# Main.net
KiCad netlist of a schematic drawn in Altium Designer
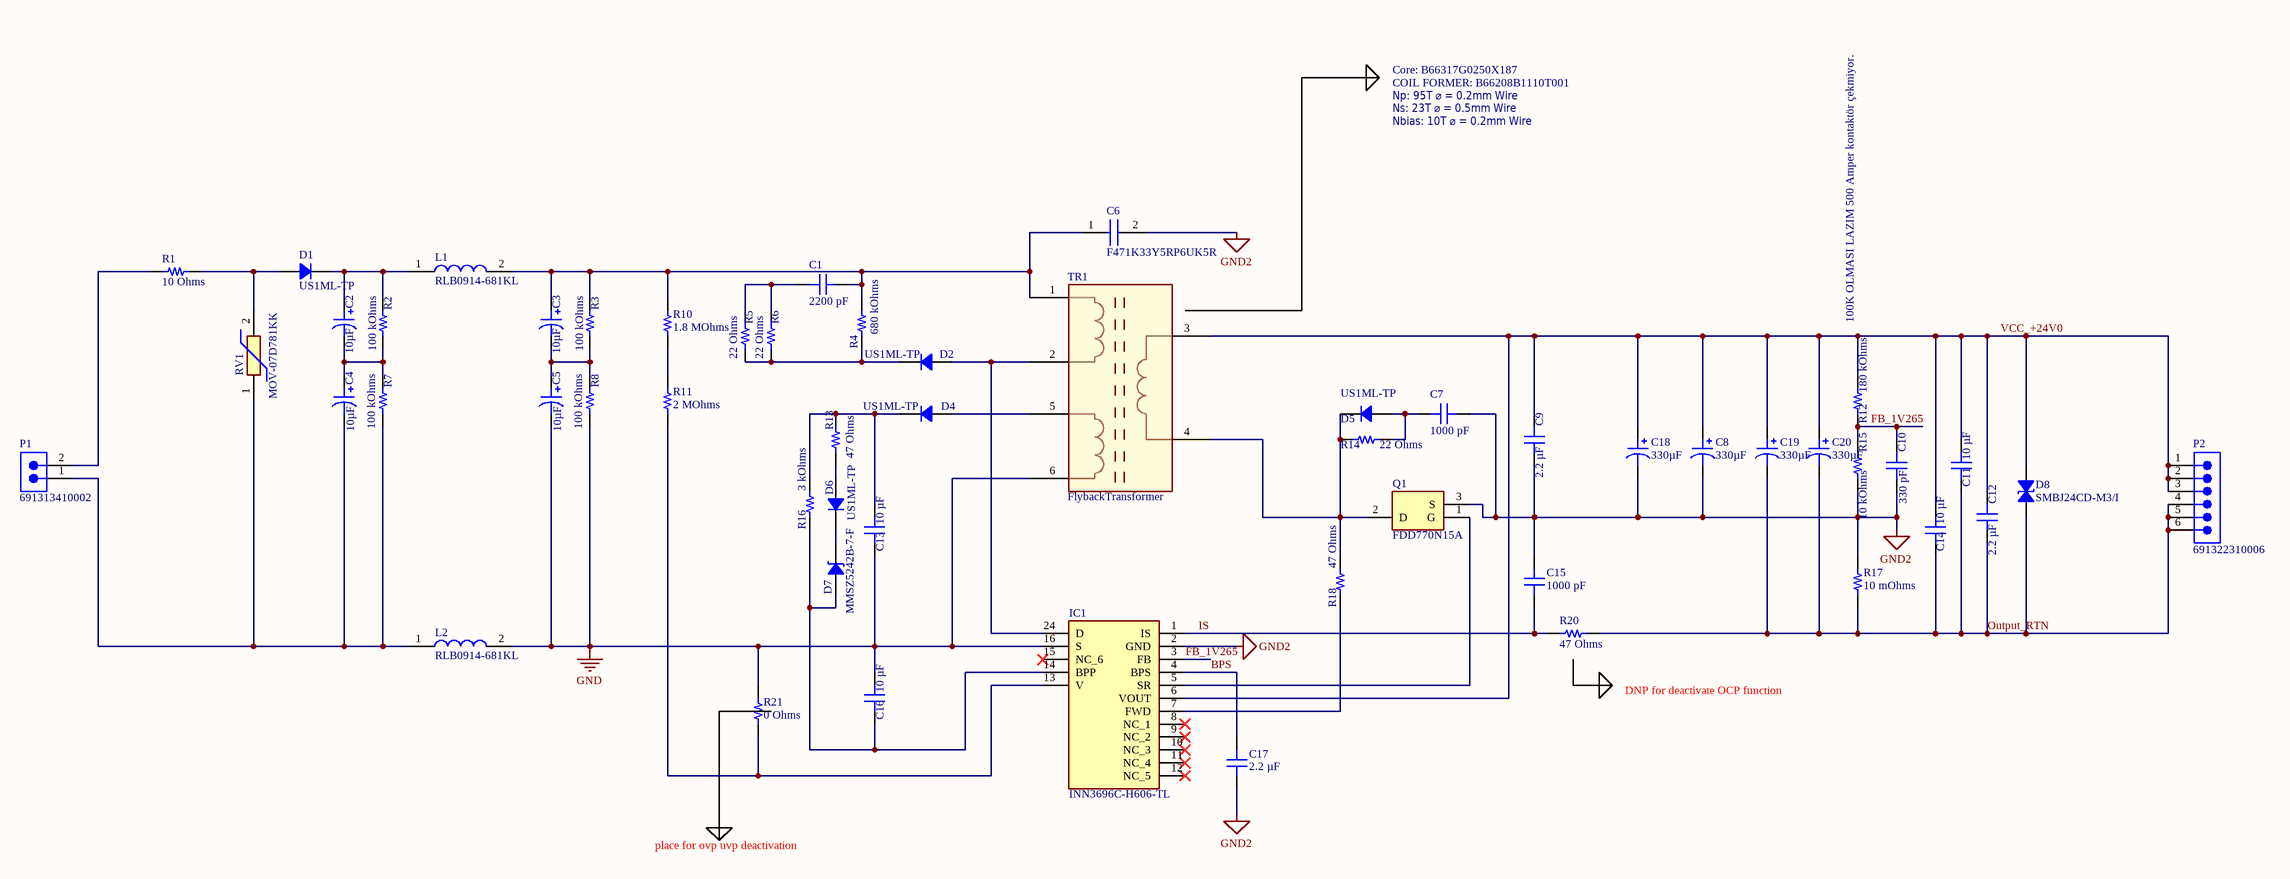
[diagram p0: Main.SchDoc]

(export (version "E")
  (design (tool "Eeschema 10.0.6"))
  (components
    (comp (ref "C1")
      (value "2200 pF")
      (footprint "CAP 1206_3216 - 0.8MM")
      (description "CAP CER 2200PF 2KV X7R 1206")
      (fields (field (name "MANUFACTURER") "KEMET") (field (name "TOLERANCE") "±10%"))
      (libsource (lib "Dannie Main") (part "CAPACITOR"))
    )
    (comp (ref "C2")
      (value "10µF")
      (footprint "CAP TH ALUM ELEC D10.00mm S5.00mm H17.00mm")
      (description "CAP ALUM 10UF 20% 400V THRUHOLE")
      (fields (field (name "PART NUMBER") "ESK106M400AH2EA") (field (name "TOLERANCE") "±20%"))
      (libsource (lib "Dannie Main") (part "POLARISED CAPACITOR"))
    )
    (comp (ref "C3")
      (value "10µF")
      (footprint "CAP TH ALUM ELEC D10.00mm S5.00mm H17.00mm")
      (description "CAP ALUM 10UF 20% 400V THRUHOLE")
      (fields (field (name "PART NUMBER") "ESK106M400AH2EA") (field (name "TOLERANCE") "±20%"))
      (libsource (lib "Dannie Main") (part "POLARISED CAPACITOR"))
    )
    (comp (ref "C4")
      (value "10µF")
      (footprint "CAP TH ALUM ELEC D10.00mm S5.00mm H17.00mm")
      (description "CAP ALUM 10UF 20% 400V THRUHOLE")
      (fields (field (name "PART NUMBER") "ESK106M400AH2EA") (field (name "TOLERANCE") "±20%"))
      (libsource (lib "Dannie Main") (part "POLARISED CAPACITOR"))
    )
    (comp (ref "C5")
      (value "10µF")
      (footprint "CAP TH ALUM ELEC D10.00mm S5.00mm H17.00mm")
      (description "CAP ALUM 10UF 20% 400V THRUHOLE")
      (fields (field (name "PART NUMBER") "ESK106M400AH2EA") (field (name "TOLERANCE") "±20%"))
      (libsource (lib "Dannie Main") (part "POLARISED CAPACITOR"))
    )
    (comp (ref "C6")
      (value "F471K33Y5RP6UK5R")
      (footprint "SamacSys:F471K33Y5RP6UK5R")
      (description "Capacitor")
      (fields (field (name "MOUSER PART NUMBER") "594-F471K33Y5RP6UK5R"))
      (libsource (lib "*") (part "F471K33Y5RP6UK5R"))
    )
    (comp (ref "C7")
      (value "1000 pF")
      (footprint "CAP 0603_1608")
      (description "CAP CER 1000PF 50V X7R 0603")
      (fields (field (name "MANUFACTURER") "Samsung Electro-Mechanics") (field (name "TOLERANCE") "±10%"))
      (libsource (lib "Dannie Main") (part "CAPACITOR"))
    )
    (comp (ref "C8")
      (value "330µF")
      (footprint "CAP TH ALUM ELEC D10.00mm S5.00mm H14.00mm")
      (description "CAP ALUM 330UF 20% 35V RADIAL")
      (fields (field (name "PART NUMBER") "UVY1V331MPD1TD") (field (name "MANUFACTURER") "Nichicon"))
      (libsource (lib "Dannie Main") (part "POLARISED CAPACITOR"))
    )
    (comp (ref "C9")
      (value "2.2 µF")
      (footprint "CAP 1206_3216 - 0.8MM")
      (description "CAP CER 2.2UF 50V X7R 1206")
      (fields (field (name "MANUFACTURER") "Samsung Electro-Mechanics") (field (name "TOLERANCE") "±10%"))
      (libsource (lib "Dannie Main") (part "CAPACITOR"))
    )
    (comp (ref "C10")
      (value "330 pF")
      (footprint "CAP 1206_3216 - 0.8MM")
      (description "CAP CER 330PF 50V X7R 1206")
      (fields (field (name "TOLERANCE") "±10%") (field (name "PART NUMBER") "885012208072"))
      (libsource (lib "Dannie Main") (part "CAPACITOR"))
    )
    (comp (ref "C11")
      (value "10 µF")
      (footprint "CAP 1206_3216 - 0.8MM")
      (description "CAP CER 10UF 50V X5R 1206")
      (fields (field (name "TOLERANCE") "±20%") (field (name "MANUFACTURER") "Samsung Electro-Mechanics"))
      (libsource (lib "Dannie Main") (part "CAPACITOR"))
    )
    (comp (ref "C12")
      (value "2.2 µF")
      (footprint "CAP 1206_3216 - 0.8MM")
      (description "CAP CER 2.2UF 50V X7R 1206")
      (fields (field (name "MANUFACTURER") "Samsung Electro-Mechanics") (field (name "TOLERANCE") "±10%"))
      (libsource (lib "Dannie Main") (part "CAPACITOR"))
    )
    (comp (ref "C13")
      (value "10 µF")
      (footprint "CAP 1206_3216 - 0.8MM")
      (description "CAP CER 10UF 50V X5R 1206")
      (fields (field (name "TOLERANCE") "±20%") (field (name "MANUFACTURER") "Samsung Electro-Mechanics"))
      (libsource (lib "Dannie Main") (part "CAPACITOR"))
    )
    (comp (ref "C14")
      (value "10 µF")
      (footprint "CAP 1206_3216 - 0.8MM")
      (description "CAP CER 10UF 50V X5R 1206")
      (fields (field (name "TOLERANCE") "±20%") (field (name "MANUFACTURER") "Samsung Electro-Mechanics"))
      (libsource (lib "Dannie Main") (part "CAPACITOR"))
    )
    (comp (ref "C15")
      (value "1000 pF")
      (footprint "CAP 0603_1608")
      (description "CAP CER 1000PF 50V X7R 0603")
      (fields (field (name "MANUFACTURER") "Samsung Electro-Mechanics") (field (name "TOLERANCE") "±10%"))
      (libsource (lib "Dannie Main") (part "CAPACITOR"))
    )
    (comp (ref "C16")
      (value "10 µF")
      (footprint "CAP 1206_3216 - 0.8MM")
      (description "CAP CER 10UF 50V X5R 1206")
      (fields (field (name "TOLERANCE") "±20%") (field (name "MANUFACTURER") "Samsung Electro-Mechanics"))
      (libsource (lib "Dannie Main") (part "CAPACITOR"))
    )
    (comp (ref "C17")
      (value "2.2 µF")
      (footprint "CAP 1206_3216 - 0.8MM")
      (description "CAP CER 2.2UF 50V X7R 1206")
      (fields (field (name "MANUFACTURER") "Samsung Electro-Mechanics") (field (name "TOLERANCE") "±10%"))
      (libsource (lib "Dannie Main") (part "CAPACITOR"))
    )
    (comp (ref "C18")
      (value "330µF")
      (footprint "CAP TH ALUM ELEC D10.00mm S5.00mm H14.00mm")
      (description "CAP ALUM 330UF 20% 35V RADIAL")
      (fields (field (name "PART NUMBER") "UVY1V331MPD1TD") (field (name "MANUFACTURER") "Nichicon"))
      (libsource (lib "Dannie Main") (part "POLARISED CAPACITOR"))
    )
    (comp (ref "C19")
      (value "330µF")
      (footprint "CAP TH ALUM ELEC D10.00mm S5.00mm H14.00mm")
      (description "CAP ALUM 330UF 20% 35V RADIAL")
      (fields (field (name "PART NUMBER") "UVY1V331MPD1TD") (field (name "MANUFACTURER") "Nichicon"))
      (libsource (lib "Dannie Main") (part "POLARISED CAPACITOR"))
    )
    (comp (ref "C20")
      (value "330µF")
      (footprint "CAP TH ALUM ELEC D10.00mm S5.00mm H14.00mm")
      (description "CAP ALUM 330UF 20% 35V RADIAL")
      (fields (field (name "PART NUMBER") "UVY1V331MPD1TD") (field (name "MANUFACTURER") "Nichicon"))
      (libsource (lib "Dannie Main") (part "POLARISED CAPACITOR"))
    )
    (comp (ref "D1")
      (value "US1ML-TP")
      (footprint "DO214AC SMA")
      (description "DIODE GEN PURP 1KV 1A DO214AC")
      (fields (field (name "MANUFACTURER") "Micro Commercial Co"))
      (libsource (lib "Dannie Main") (part "DIODE"))
    )
    (comp (ref "D2")
      (value "US1ML-TP")
      (footprint "DO214AC SMA")
      (description "DIODE GEN PURP 1KV 1A DO214AC")
      (fields (field (name "MANUFACTURER") "Micro Commercial Co"))
      (libsource (lib "Dannie Main") (part "DIODE"))
    )
    (comp (ref "D4")
      (value "US1ML-TP")
      (footprint "DO214AC SMA")
      (description "DIODE GEN PURP 1KV 1A DO214AC")
      (fields (field (name "MANUFACTURER") "Micro Commercial Co"))
      (libsource (lib "Dannie Main") (part "DIODE"))
    )
    (comp (ref "D5")
      (value "US1ML-TP")
      (footprint "DO214AC SMA")
      (description "DIODE GEN PURP 1KV 1A DO214AC")
      (fields (field (name "MANUFACTURER") "Micro Commercial Co"))
      (libsource (lib "Dannie Main") (part "DIODE"))
    )
    (comp (ref "D6")
      (value "US1ML-TP")
      (footprint "DO214AC SMA")
      (description "DIODE GEN PURP 1KV 1A DO214AC")
      (fields (field (name "MANUFACTURER") "Micro Commercial Co"))
      (libsource (lib "Dannie Main") (part "DIODE"))
    )
    (comp (ref "D7")
      (value "MMSZ5242B-7-F")
      (footprint "SOD-123")
      (description "DIODE ZENER 12V 500MW SOD123")
      (fields (field (name "MANUFACTURER") "Diodes Incorporated") (field (name "TOLERANCE") "±5%"))
      (libsource (lib "Dannie Main") (part "DIODE ZENER"))
    )
    (comp (ref "D8")
      (value "SMBJ24CD-M3/I")
      (footprint "DO214AA SMB")
      (description "TVS DIODE 24V 38.4V DO214AA")
      (fields (field (name "MANUFACTURER") "Vishay Semiconductor Diodes Division"))
      (libsource (lib "Dannie Main") (part "DIODE TVS"))
    )
    (comp (ref "IC1")
      (value "INN3696C-H606-TL")
      (footprint "INN3696CH606TL")
      (description "AC/DC Converters 35W 230VAC 30W 15mW 900V FET")
      (fields (field (name "MOUSER PART NUMBER") "869-INN3696C-H606-TL"))
      (libsource (lib "Dannie Main") (part "INN3696C-H606-TL"))
    )
    (comp (ref "L1")
      (value "RLB0914-681KL")
      (footprint "SamacSys:RLB0914681KL")
      (description "Inductor")
      (fields (field (name "MOUSER PART NUMBER") "652-RLB0914-681KL"))
      (libsource (lib "*") (part "RLB0914-681KL"))
    )
    (comp (ref "L2")
      (value "RLB0914-681KL")
      (footprint "SamacSys:RLB0914681KL")
      (description "Inductor")
      (fields (field (name "MOUSER PART NUMBER") "652-RLB0914-681KL"))
      (libsource (lib "*") (part "RLB0914-681KL"))
    )
    (comp (ref "P1")
      (value "691313410002")
      (footprint "691313410002")
      (description "WR-TBL Series 3134 Close Horizontal PCB Header, THT, pitch 7.62mm, 2p")
      (fields (field (name "MANUFACTURER") "Wurth Elektronik"))
      (libsource (lib "Dannie Main") (part "TBL - 1R - 02P - Male"))
    )
    (comp (ref "P2")
      (value "691322310006")
      (footprint "691322310006")
      (description "WR-TBL Series 322 Horizontal PCB Header, THT, pitch 3.81mm, 6p")
      (fields (field (name "MANUFACTURER") "Wurth Elektronik"))
      (libsource (lib "Dannie Main") (part "TBL - 1R - 06P - Male"))
    )
    (comp (ref "Q1")
      (value "FDD770N15A")
      (footprint "SamacSys:FDD770N15A")
      (description "Transistor")
      (fields (field (name "MOUSER PART NUMBER") "512-FDD770N15A"))
      (libsource (lib "*") (part "FDD770N15A"))
    )
    (comp (ref "R1")
      (value "10 Ohms")
      (footprint "RES 2512_6432")
      (description "RES 10 OHM 5% 1W 2512")
      (fields (field (name "TOLERANCE") "±5%") (field (name "PART NUMBER") "RMCF2512JT10R0"))
      (libsource (lib "Dannie Main") (part "RESISTOR"))
    )
    (comp (ref "R2")
      (value "100 kOhms")
      (footprint "RES 1206_3216")
      (description "RES 100K OHM 1% 1/4W 1206")
      (fields
        (field (name "PART NUMBER") "RMCF1206FT100K")
        (field (name "MANUFACTURER") "Stackpole Electronics Inc")
      )
      (libsource (lib "Dannie Main") (part "RESISTOR"))
    )
    (comp (ref "R3")
      (value "100 kOhms")
      (footprint "RES 1206_3216")
      (description "RES 100K OHM 1% 1/4W 1206")
      (fields
        (field (name "PART NUMBER") "RMCF1206FT100K")
        (field (name "MANUFACTURER") "Stackpole Electronics Inc")
      )
      (libsource (lib "Dannie Main") (part "RESISTOR"))
    )
    (comp (ref "R4")
      (value "680 kOhms")
      (footprint "RES 1206_3216")
      (description "RES 680K OHM 1% 1/4W 1206")
      (fields (field (name "PART NUMBER") "RC1206FR-07680KL") (field (name "MANUFACTURER") "Yageo"))
      (libsource (lib "Dannie Main") (part "RESISTOR"))
    )
    (comp (ref "R5")
      (value "22 Ohms")
      (footprint "RES 1206_3216")
      (description "RES 22 OHM 5% 1/2W 1206")
      (fields (field (name "MANUFACTURER") "Yageo") (field (name "TOLERANCE") "±5%"))
      (libsource (lib "Dannie Main") (part "RESISTOR"))
    )
    (comp (ref "R6")
      (value "22 Ohms")
      (footprint "RES 1206_3216")
      (description "RES 22 OHM 5% 1/2W 1206")
      (fields (field (name "MANUFACTURER") "Yageo") (field (name "TOLERANCE") "±5%"))
      (libsource (lib "Dannie Main") (part "RESISTOR"))
    )
    (comp (ref "R7")
      (value "100 kOhms")
      (footprint "RES 1206_3216")
      (description "RES 100K OHM 1% 1/4W 1206")
      (fields
        (field (name "PART NUMBER") "RMCF1206FT100K")
        (field (name "MANUFACTURER") "Stackpole Electronics Inc")
      )
      (libsource (lib "Dannie Main") (part "RESISTOR"))
    )
    (comp (ref "R8")
      (value "100 kOhms")
      (footprint "RES 1206_3216")
      (description "RES 100K OHM 1% 1/4W 1206")
      (fields
        (field (name "PART NUMBER") "RMCF1206FT100K")
        (field (name "MANUFACTURER") "Stackpole Electronics Inc")
      )
      (libsource (lib "Dannie Main") (part "RESISTOR"))
    )
    (comp (ref "R10")
      (value "1.8 MOhms")
      (footprint "RES 1206_3216")
      (description "RES 1.8M OHM 1% 1/4W 1206")
      (fields (field (name "MANUFACTURER") "Yageo") (field (name "PART NUMBER") "RC1206FR-071M8L"))
      (libsource (lib "Dannie Main") (part "RESISTOR"))
    )
    (comp (ref "R11")
      (value "2 MOhms")
      (footprint "RES 1206_3216")
      (description "RES 2M OHM 5% 1/4W 1206")
      (fields (field (name "TOLERANCE") "±5%") (field (name "PART NUMBER") "RC1206JR-072ML"))
      (libsource (lib "Dannie Main") (part "RESISTOR"))
    )
    (comp (ref "R12")
      (value "180 kOhms")
      (footprint "RES 1206_3216")
      (description "RES 180K OHM 5% 1/4W 1206")
      (fields (field (name "MANUFACTURER") "Yageo") (field (name "PART NUMBER") "RC1206JR-07180KL"))
      (libsource (lib "Dannie Main") (part "RESISTOR"))
    )
    (comp (ref "R13")
      (value "47 Ohms")
      (footprint "RES 1206_3216")
      (description "RES 47 OHM 5% 1/4W 1206")
      (fields (field (name "PART NUMBER") "RC1206JR-0747RL") (field (name "MANUFACTURER") "Yageo"))
      (libsource (lib "Dannie Main") (part "RESISTOR"))
    )
    (comp (ref "R14")
      (value "22 Ohms")
      (footprint "RES 1206_3216")
      (description "RES 22 OHM 5% 1/2W 1206")
      (fields (field (name "MANUFACTURER") "Yageo") (field (name "TOLERANCE") "±5%"))
      (libsource (lib "Dannie Main") (part "RESISTOR"))
    )
    (comp (ref "R15")
      (value "10 kOhms")
      (footprint "RES 1206_3216")
      (description "RES 10K OHM 1% 1/4W 1206")
      (fields (field (name "MANUFACTURER") "Yageo") (field (name "TOLERANCE") "±1%"))
      (libsource (lib "Dannie Main") (part "RESISTOR"))
    )
    (comp (ref "R16")
      (value "3 kOhms")
      (footprint "RES 1206_3216")
      (description "RES 3K OHM 5% 1/4W 1206")
      (fields (field (name "TOLERANCE") "±5%") (field (name "PART NUMBER") "RC1206JR-073KL"))
      (libsource (lib "Dannie Main") (part "RESISTOR"))
    )
    (comp (ref "R17")
      (value "10 mOhms")
      (footprint "RES 1206_3216")
      (description "RES 0.01 OHM 1% 1/4W 1206")
      (fields (field (name "TOLERANCE") "±1%") (field (name "PART NUMBER") "PA1206FRE070R01Z"))
      (libsource (lib "Dannie Main") (part "RESISTOR"))
    )
    (comp (ref "R18")
      (value "47 Ohms")
      (footprint "RES 1206_3216")
      (description "RES 47 OHM 5% 1/4W 1206")
      (fields (field (name "PART NUMBER") "RC1206JR-0747RL") (field (name "MANUFACTURER") "Yageo"))
      (libsource (lib "Dannie Main") (part "RESISTOR"))
    )
    (comp (ref "R20")
      (value "47 Ohms")
      (footprint "RES 1206_3216")
      (description "RES 47 OHM 5% 1/4W 1206")
      (fields (field (name "PART NUMBER") "RC1206JR-0747RL") (field (name "MANUFACTURER") "Yageo"))
      (libsource (lib "Dannie Main") (part "RESISTOR"))
    )
    (comp (ref "R21")
      (value "0 Ohms")
      (footprint "RES 1206_3216")
      (description "RES 0 OHM JUMPER 1/4W 1206")
      (fields (field (name "MANUFACTURER") "Yageo") (field (name "PART NUMBER") "RC1206JR-070RL"))
      (libsource (lib "Dannie Main") (part "RESISTOR"))
    )
    (comp (ref "RV1")
      (value "MOV-07D781KK")
      (footprint "SamacSys:MOV07D781KK")
      (description "Varistor")
      (libsource (lib "*") (part "MOV-07D781KK"))
    )
    (comp (ref "TR1")
      (value "FlybackTransformer")
      (footprint "FlybackTransformer")
      (description "B66317G0160X187 GAPPED N87 CORE")
      (fields (field (name "MANUFACTURER_PART_NUMBER") "B66317G0160X187"))
      (libsource (lib "Dannie Main") (part "FlybackTransformer"))
    )
  )
  (nets
    (net (code "1") (name "/BPS") (class "Default")
      (node (ref "C17") (pin "1") (pinfunction "1_1") (pintype "passive"))
      (node (ref "IC1") (pin "4") (pinfunction "BPS_4") (pintype "passive"))
    )
    (net (code "2") (name "/FB_1V265") (class "Default")
      (node (ref "C10") (pin "2") (pinfunction "2_2") (pintype "passive"))
      (node (ref "IC1") (pin "3") (pinfunction "FB_3") (pintype "passive"))
      (node (ref "R12") (pin "1") (pinfunction "1_1") (pintype "passive"))
      (node (ref "R15") (pin "2") (pinfunction "2_2") (pintype "passive"))
    )
    (net (code "3") (name "/IS") (class "Default")
      (node (ref "C15") (pin "1") (pinfunction "1_1") (pintype "passive"))
      (node (ref "IC1") (pin "1") (pinfunction "IS_1") (pintype "passive"))
      (node (ref "R20") (pin "2") (pinfunction "2_2") (pintype "passive"))
    )
    (net (code "4") (name "/Output_RTN") (class "Default")
      (node (ref "C11") (pin "1") (pinfunction "1_1") (pintype "passive"))
      (node (ref "C12") (pin "1") (pinfunction "1_1") (pintype "passive"))
      (node (ref "C14") (pin "1") (pinfunction "1_1") (pintype "passive"))
      (node (ref "C19") (pin "2") (pinfunction "2_2") (pintype "passive"))
      (node (ref "C20") (pin "2") (pinfunction "2_2") (pintype "passive"))
      (node (ref "D8") (pin "1") (pinfunction "1_1") (pintype "passive"))
      (node (ref "P2") (pin "4") (pinfunction "4_4") (pintype "passive"))
      (node (ref "P2") (pin "5") (pinfunction "5_5") (pintype "passive"))
      (node (ref "P2") (pin "6") (pinfunction "6_6") (pintype "passive"))
      (node (ref "R17") (pin "1") (pinfunction "1_1") (pintype "passive"))
      (node (ref "R20") (pin "1") (pinfunction "1_1") (pintype "passive"))
    )
    (net (code "5") (name "/VCC_+24V0") (class "Default")
      (node (ref "C11") (pin "2") (pinfunction "2_2") (pintype "passive"))
      (node (ref "C12") (pin "2") (pinfunction "2_2") (pintype "passive"))
      (node (ref "C14") (pin "2") (pinfunction "2_2") (pintype "passive"))
      (node (ref "C18") (pin "1") (pinfunction "1_1") (pintype "passive"))
      (node (ref "C19") (pin "1") (pinfunction "1_1") (pintype "passive"))
      (node (ref "C20") (pin "1") (pinfunction "1_1") (pintype "passive"))
      (node (ref "C8") (pin "1") (pinfunction "1_1") (pintype "passive"))
      (node (ref "C9") (pin "2") (pinfunction "2_2") (pintype "passive"))
      (node (ref "D8") (pin "2") (pinfunction "2_2") (pintype "passive"))
      (node (ref "IC1") (pin "6") (pinfunction "VOUT_6") (pintype "passive"))
      (node (ref "P2") (pin "1") (pinfunction "1_1") (pintype "passive"))
      (node (ref "P2") (pin "2") (pinfunction "2_2") (pintype "passive"))
      (node (ref "P2") (pin "3") (pinfunction "3_3") (pintype "passive"))
      (node (ref "R12") (pin "2") (pinfunction "2_2") (pintype "passive"))
      (node (ref "TR1") (pin "3") (pinfunction "3_3") (pintype "passive"))
    )
    (net (code "6") (name "GND") (class "Default")
      (node (ref "C13") (pin "1") (pinfunction "1_1") (pintype "passive"))
      (node (ref "C16") (pin "2") (pinfunction "2_2") (pintype "passive"))
      (node (ref "C5") (pin "2") (pinfunction "2_2") (pintype "passive"))
      (node (ref "IC1") (pin "16") (pinfunction "S_16") (pintype "passive"))
      (node (ref "L2") (pin "2") (pinfunction "2_2") (pintype "passive"))
      (node (ref "R21") (pin "2") (pinfunction "2_2") (pintype "passive"))
      (node (ref "R8") (pin "1") (pinfunction "1_1") (pintype "passive"))
      (node (ref "TR1") (pin "6") (pinfunction "6_6") (pintype "passive"))
    )
    (net (code "7") (name "GND2") (class "Default")
      (node (ref "C10") (pin "1") (pinfunction "1_1") (pintype "passive"))
      (node (ref "C15") (pin "2") (pinfunction "2_2") (pintype "passive"))
      (node (ref "C17") (pin "2") (pinfunction "2_2") (pintype "passive"))
      (node (ref "C18") (pin "2") (pinfunction "2_2") (pintype "passive"))
      (node (ref "C6") (pin "2") (pinfunction "2_2") (pintype "passive"))
      (node (ref "C7") (pin "2") (pinfunction "2_2") (pintype "passive"))
      (node (ref "C8") (pin "2") (pinfunction "2_2") (pintype "passive"))
      (node (ref "C9") (pin "1") (pinfunction "1_1") (pintype "passive"))
      (node (ref "IC1") (pin "2") (pinfunction "GND_2") (pintype "passive"))
      (node (ref "Q1") (pin "3") (pinfunction "S_3") (pintype "passive"))
      (node (ref "R15") (pin "1") (pinfunction "1_1") (pintype "passive"))
      (node (ref "R17") (pin "2") (pinfunction "2_2") (pintype "passive"))
    )
    (net (code "8") (name "Net-(C1-Pad1)") (class "Default")
      (node (ref "C1") (pin "1") (pinfunction "1_1") (pintype "passive"))
      (node (ref "R5") (pin "2") (pinfunction "2_2") (pintype "passive"))
      (node (ref "R6") (pin "2") (pinfunction "2_2") (pintype "passive"))
    )
    (net (code "9") (name "Net-(C1-Pad2)") (class "Default")
      (node (ref "C1") (pin "2") (pinfunction "2_2") (pintype "passive"))
      (node (ref "C3") (pin "1") (pinfunction "1_1") (pintype "passive"))
      (node (ref "C6") (pin "1") (pinfunction "1_1") (pintype "passive"))
      (node (ref "L1") (pin "2") (pinfunction "2_2") (pintype "passive"))
      (node (ref "R10") (pin "2") (pinfunction "2_2") (pintype "passive"))
      (node (ref "R3") (pin "2") (pinfunction "2_2") (pintype "passive"))
      (node (ref "R4") (pin "2") (pinfunction "2_2") (pintype "passive"))
      (node (ref "TR1") (pin "1") (pintype "passive"))
    )
    (net (code "10") (name "Net-(C2-Pad1)") (class "Default")
      (node (ref "C2") (pin "1") (pinfunction "1_1") (pintype "passive"))
      (node (ref "D1") (pin "2") (pinfunction "2_2") (pintype "passive"))
      (node (ref "L1") (pin "1") (pinfunction "1_1") (pintype "passive"))
      (node (ref "R2") (pin "2") (pinfunction "2_2") (pintype "passive"))
    )
    (net (code "11") (name "Net-(C2-Pad2)") (class "Default")
      (node (ref "C2") (pin "2") (pinfunction "2_2") (pintype "passive"))
      (node (ref "C4") (pin "1") (pinfunction "1_1") (pintype "passive"))
      (node (ref "R2") (pin "1") (pinfunction "1_1") (pintype "passive"))
      (node (ref "R7") (pin "2") (pinfunction "2_2") (pintype "passive"))
    )
    (net (code "12") (name "Net-(C3-Pad2)") (class "Default")
      (node (ref "C3") (pin "2") (pinfunction "2_2") (pintype "passive"))
      (node (ref "C5") (pin "1") (pinfunction "1_1") (pintype "passive"))
      (node (ref "R3") (pin "1") (pinfunction "1_1") (pintype "passive"))
      (node (ref "R8") (pin "2") (pinfunction "2_2") (pintype "passive"))
    )
    (net (code "13") (name "Net-(C4-Pad2)") (class "Default")
      (node (ref "C4") (pin "2") (pinfunction "2_2") (pintype "passive"))
      (node (ref "L2") (pin "1") (pinfunction "1_1") (pintype "passive"))
      (node (ref "P1") (pin "1") (pinfunction "1_1") (pintype "passive"))
      (node (ref "R7") (pin "1") (pinfunction "1_1") (pintype "passive"))
      (node (ref "RV1") (pin "1") (pinfunction "1_1") (pintype "passive"))
    )
    (net (code "14") (name "Net-(C7-Pad1)") (class "Default")
      (node (ref "C7") (pin "1") (pinfunction "1_1") (pintype "passive"))
      (node (ref "D5") (pin "1") (pinfunction "1_1") (pintype "passive"))
      (node (ref "R14") (pin "1") (pinfunction "1_1") (pintype "passive"))
    )
    (net (code "15") (name "Net-(C13-Pad2)") (class "Default")
      (node (ref "C13") (pin "2") (pinfunction "2_2") (pintype "passive"))
      (node (ref "D4") (pin "2") (pinfunction "2_2") (pintype "passive"))
      (node (ref "R13") (pin "2") (pinfunction "2_2") (pintype "passive"))
      (node (ref "R16") (pin "2") (pinfunction "2_2") (pintype "passive"))
    )
    (net (code "16") (name "Net-(D1-Pad1)") (class "Default")
      (node (ref "D1") (pin "1") (pinfunction "1_1") (pintype "passive"))
      (node (ref "R1") (pin "2") (pinfunction "2_2") (pintype "passive"))
      (node (ref "RV1") (pin "2") (pinfunction "2_2") (pintype "passive"))
    )
    (net (code "17") (name "Net-(D2-Pad2)") (class "Default")
      (node (ref "D2") (pin "2") (pinfunction "2_2") (pintype "passive"))
      (node (ref "R4") (pin "1") (pinfunction "1_1") (pintype "passive"))
      (node (ref "R5") (pin "1") (pinfunction "1_1") (pintype "passive"))
      (node (ref "R6") (pin "1") (pinfunction "1_1") (pintype "passive"))
    )
    (net (code "18") (name "Net-(D4-Pad1)") (class "Default")
      (node (ref "D4") (pin "1") (pinfunction "1_1") (pintype "passive"))
      (node (ref "TR1") (pin "5") (pinfunction "5_5") (pintype "passive"))
    )
    (net (code "19") (name "Net-(D6-Pad1)") (class "Default")
      (node (ref "D6") (pin "1") (pinfunction "1_1") (pintype "passive"))
      (node (ref "R13") (pin "1") (pinfunction "1_1") (pintype "passive"))
    )
    (net (code "20") (name "Net-(D6-Pad2)") (class "Default")
      (node (ref "D6") (pin "2") (pinfunction "2_2") (pintype "passive"))
      (node (ref "D7") (pin "2") (pinfunction "2_2") (pintype "passive"))
    )
    (net (code "21") (name "Net-(IC1-BPP)") (class "Default")
      (node (ref "C16") (pin "1") (pinfunction "1_1") (pintype "passive"))
      (node (ref "D7") (pin "1") (pinfunction "1_1") (pintype "passive"))
      (node (ref "IC1") (pin "14") (pinfunction "BPP_14") (pintype "passive"))
      (node (ref "R16") (pin "1") (pinfunction "1_1") (pintype "passive"))
    )
    (net (code "22") (name "Net-(IC1-D)") (class "Default")
      (node (ref "D2") (pin "1") (pinfunction "1_1") (pintype "passive"))
      (node (ref "IC1") (pin "24") (pinfunction "D_24") (pintype "passive"))
      (node (ref "TR1") (pin "2") (pinfunction "2_2") (pintype "passive"))
    )
    (net (code "23") (name "Net-(IC1-FWD)") (class "Default")
      (node (ref "IC1") (pin "7") (pinfunction "FWD_7") (pintype "passive"))
      (node (ref "R18") (pin "1") (pinfunction "1_1") (pintype "passive"))
    )
    (net (code "24") (name "Net-(IC1-SR)") (class "Default")
      (node (ref "IC1") (pin "5") (pinfunction "SR_5") (pintype "passive"))
      (node (ref "Q1") (pin "1") (pinfunction "G_1") (pintype "passive"))
    )
    (net (code "25") (name "Net-(IC1-V)") (class "Default")
      (node (ref "IC1") (pin "13") (pinfunction "V_13") (pintype "passive"))
      (node (ref "R11") (pin "1") (pinfunction "1_1") (pintype "passive"))
      (node (ref "R21") (pin "1") (pinfunction "1_1") (pintype "passive"))
    )
    (net (code "26") (name "Net-(P1-Pad2)") (class "Default")
      (node (ref "P1") (pin "2") (pinfunction "2_2") (pintype "passive"))
      (node (ref "R1") (pin "1") (pinfunction "1_1") (pintype "passive"))
    )
    (net (code "27") (name "Net-(Q1-D)") (class "Default")
      (node (ref "D5") (pin "2") (pinfunction "2_2") (pintype "passive"))
      (node (ref "Q1") (pin "2") (pinfunction "D_2") (pintype "passive"))
      (node (ref "R14") (pin "2") (pinfunction "2_2") (pintype "passive"))
      (node (ref "R18") (pin "2") (pinfunction "2_2") (pintype "passive"))
      (node (ref "TR1") (pin "4") (pinfunction "4_4") (pintype "passive"))
    )
    (net (code "28") (name "Net-(R10-Pad1)") (class "Default")
      (node (ref "R10") (pin "1") (pinfunction "1_1") (pintype "passive"))
      (node (ref "R11") (pin "2") (pinfunction "2_2") (pintype "passive"))
    )
    (net (code "29") (name "unconnected-(IC1-NC_1-Pad8)") (class "Default")
      (node (ref "IC1") (pin "8") (pinfunction "NC_1_8") (pintype "passive+no_connect"))
    )
    (net (code "30") (name "unconnected-(IC1-NC_2-Pad9)") (class "Default")
      (node (ref "IC1") (pin "9") (pinfunction "NC_2_9") (pintype "passive+no_connect"))
    )
    (net (code "31") (name "unconnected-(IC1-NC_3-Pad10)") (class "Default")
      (node (ref "IC1") (pin "10") (pinfunction "NC_3_10") (pintype "passive+no_connect"))
    )
    (net (code "32") (name "unconnected-(IC1-NC_4-Pad11)") (class "Default")
      (node (ref "IC1") (pin "11") (pinfunction "NC_4_11") (pintype "passive+no_connect"))
    )
    (net (code "33") (name "unconnected-(IC1-NC_5-Pad12)") (class "Default")
      (node (ref "IC1") (pin "12") (pinfunction "NC_5_12") (pintype "passive+no_connect"))
    )
    (net (code "34") (name "unconnected-(IC1-NC_6-Pad15)") (class "Default")
      (node (ref "IC1") (pin "15") (pinfunction "NC_6_15") (pintype "passive+no_connect"))
    )
  )
)
